# Bluetooth.net
KiCad netlist of a schematic drawn in Altium Designer
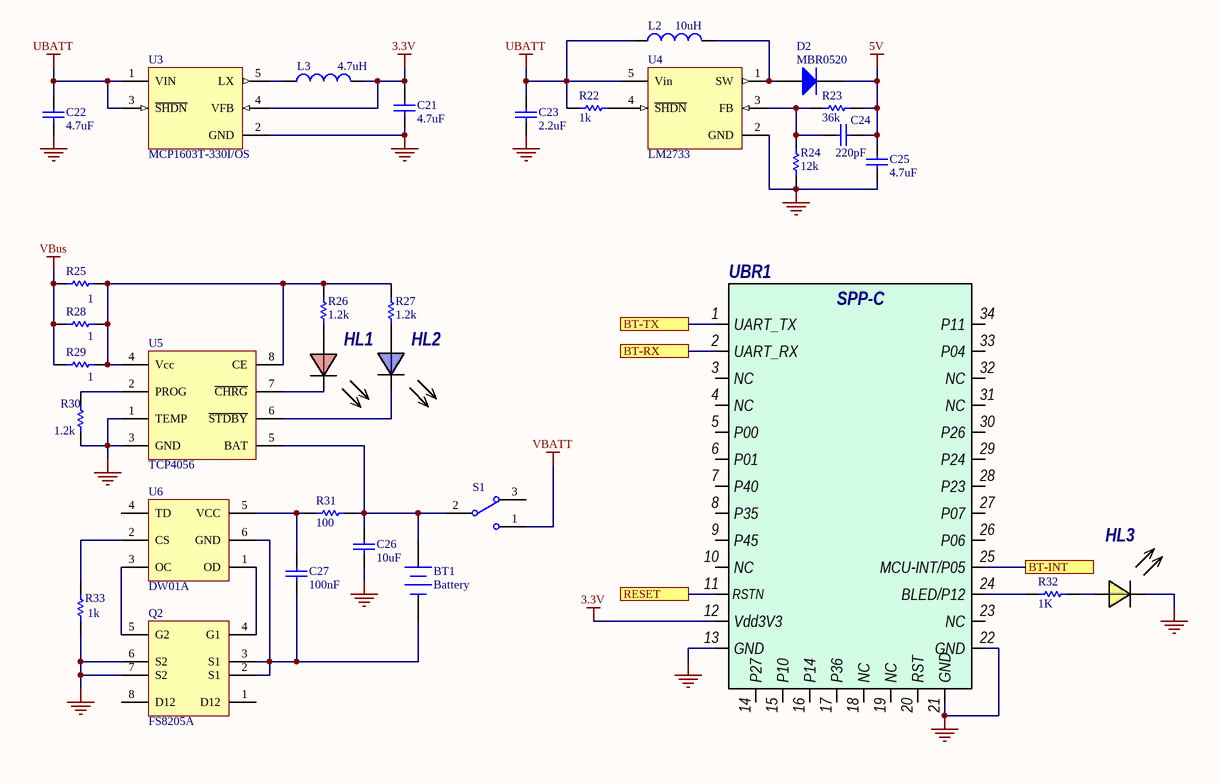
[diagram p0: Bluetooth.SchDoc]

(export (version "E")
  (design (tool "Eeschema 10.0.6"))
  (components
    (comp (ref "BT1")
      (value "Battery")
      (footprint "BAT-2")
      (description "Multicell Battery")
      (fields (field (name "PUBLISHER") "Altium Limited"))
      (libsource (lib "Miscellaneous Devices") (part "Battery"))
    )
    (comp (ref "C21")
      (value "4.7uF")
      (footprint "RAD-0.3")
      (description "Capacitor")
      (fields (field (name "Comment") "Cap") (field (name "PUBLISHER") "Altium Limited"))
      (libsource (lib "Miscellaneous Devices") (part "Cap"))
    )
    (comp (ref "C22")
      (value "4.7uF")
      (footprint "RAD-0.3")
      (description "Capacitor")
      (fields (field (name "Comment") "Cap") (field (name "PUBLISHER") "Altium Limited"))
      (libsource (lib "Miscellaneous Devices") (part "Cap"))
    )
    (comp (ref "C23")
      (value "2.2uF")
      (footprint "RAD-0.3")
      (description "Capacitor")
      (fields (field (name "Comment") "Cap") (field (name "PUBLISHER") "Altium Limited"))
      (libsource (lib "Miscellaneous Devices") (part "Cap"))
    )
    (comp (ref "C24")
      (value "220pF")
      (footprint "RAD-0.3")
      (description "Capacitor")
      (fields (field (name "Comment") "Cap") (field (name "PUBLISHER") "Altium Limited"))
      (libsource (lib "Miscellaneous Devices") (part "Cap"))
    )
    (comp (ref "C25")
      (value "4.7uF")
      (footprint "RAD-0.3")
      (description "Capacitor")
      (fields (field (name "Comment") "Cap") (field (name "PUBLISHER") "Altium Limited"))
      (libsource (lib "Miscellaneous Devices") (part "Cap"))
    )
    (comp (ref "C26")
      (value "10uF")
      (footprint "RAD-0.3")
      (description "Capacitor")
      (fields (field (name "Comment") "Cap") (field (name "PUBLISHER") "Altium Limited"))
      (libsource (lib "Miscellaneous Devices") (part "Cap"))
    )
    (comp (ref "C27")
      (value "100nF")
      (footprint "RAD-0.3")
      (description "Capacitor")
      (fields (field (name "Comment") "Cap") (field (name "PUBLISHER") "Altium Limited"))
      (libsource (lib "Miscellaneous Devices") (part "Cap"))
    )
    (comp (ref "D2")
      (value "MBR0520")
      (footprint "SOD323/A")
      (description "BAT60JFILM")
      (fields (field (name "PUBLISHER") "Altium Limited"))
      (libsource (lib "MB997") (part "BAT60JFILM"))
    )
    (comp (ref "HL1")
      (value "LED_Red")
      (footprint "0603_Red")
      (description "LED Red")
      (libsource (lib "Opto") (part "LED_Red"))
    )
    (comp (ref "HL2")
      (value "LED_Blue")
      (footprint "0603_Blue")
      (description "LED Blue")
      (libsource (lib "Opto") (part "LED_Blue"))
    )
    (comp (ref "HL3")
      (value "Yellow")
      (footprint "0603_Yellow")
      (description "LED Yellow")
      (libsource (lib "Opto") (part "LED_Yellow"))
    )
    (comp (ref "L2")
      (value "10uH")
      (footprint "0402-A")
      (description "Inductor")
      (fields (field (name "PUBLISHER") "Altium Limited"))
      (libsource (lib "Miscellaneous Devices") (part "Inductor"))
    )
    (comp (ref "L3")
      (value "4.7uH")
      (footprint "0402-A")
      (description "Inductor")
      (fields (field (name "PUBLISHER") "Altium Limited"))
      (libsource (lib "Miscellaneous Devices") (part "Inductor"))
    )
    (comp (ref "Q2") (value "FS8205A") (footprint "TSSOP8") (libsource (lib "AU9254") (part "FS8205A")))
    (comp (ref "R22")
      (value "1k")
      (footprint "AXIAL-0.3")
      (description "Resistor")
      (fields (field (name "Comment") "Res1") (field (name "PUBLISHER") "Altium Limited"))
      (libsource (lib "Miscellaneous Devices") (part "Res1"))
    )
    (comp (ref "R23")
      (value "36k")
      (footprint "AXIAL-0.3")
      (description "Resistor")
      (fields (field (name "Comment") "Res1") (field (name "PUBLISHER") "Altium Limited"))
      (libsource (lib "Miscellaneous Devices") (part "Res1"))
    )
    (comp (ref "R24")
      (value "12k")
      (footprint "AXIAL-0.3")
      (description "Resistor")
      (fields (field (name "Comment") "Res1") (field (name "PUBLISHER") "Altium Limited"))
      (libsource (lib "Miscellaneous Devices") (part "Res1"))
    )
    (comp (ref "R25")
      (value "1")
      (footprint "AXIAL-0.3")
      (description "Resistor")
      (fields (field (name "Comment") "Res1") (field (name "PUBLISHER") "Altium Limited"))
      (libsource (lib "Miscellaneous Devices") (part "Res1"))
    )
    (comp (ref "R26")
      (value "1.2k")
      (footprint "AXIAL-0.3")
      (description "Resistor")
      (fields (field (name "Comment") "Res1") (field (name "PUBLISHER") "Altium Limited"))
      (libsource (lib "Miscellaneous Devices") (part "Res1"))
    )
    (comp (ref "R27")
      (value "1.2k")
      (footprint "AXIAL-0.3")
      (description "Resistor")
      (fields (field (name "Comment") "Res1") (field (name "PUBLISHER") "Altium Limited"))
      (libsource (lib "Miscellaneous Devices") (part "Res1"))
    )
    (comp (ref "R28")
      (value "1")
      (footprint "AXIAL-0.3")
      (description "Resistor")
      (fields (field (name "Comment") "Res1") (field (name "PUBLISHER") "Altium Limited"))
      (libsource (lib "Miscellaneous Devices") (part "Res1"))
    )
    (comp (ref "R29")
      (value "1")
      (footprint "AXIAL-0.3")
      (description "Resistor")
      (fields (field (name "Comment") "Res1") (field (name "PUBLISHER") "Altium Limited"))
      (libsource (lib "Miscellaneous Devices") (part "Res1"))
    )
    (comp (ref "R30")
      (value "1.2k")
      (footprint "AXIAL-0.3")
      (description "Resistor")
      (fields (field (name "Comment") "Res1") (field (name "PUBLISHER") "Altium Limited"))
      (libsource (lib "Miscellaneous Devices") (part "Res1"))
    )
    (comp (ref "R31")
      (value "100")
      (footprint "AXIAL-0.3")
      (description "Resistor")
      (fields (field (name "Comment") "Res1") (field (name "PUBLISHER") "Altium Limited"))
      (libsource (lib "Miscellaneous Devices") (part "Res1"))
    )
    (comp (ref "R32")
      (value "1K")
      (footprint "AXIAL-0.3")
      (description "Resistor")
      (fields (field (name "Comment") "Res1") (field (name "PUBLISHER") "Altium Limited"))
      (libsource (lib "Miscellaneous Devices") (part "Res1"))
    )
    (comp (ref "R33")
      (value "1k")
      (footprint "AXIAL-0.3")
      (description "Resistor")
      (fields (field (name "Comment") "Res1") (field (name "PUBLISHER") "Altium Limited"))
      (libsource (lib "Miscellaneous Devices") (part "Res1"))
    )
    (comp (ref "S1")
      (value "SW-SPDT")
      (footprint "TL36WW15050")
      (description "SPDT Subminiature Toggle Switch, Right Angle Mounting, Vertical Actuation")
      (fields (field (name "PUBLISHER") "Altium Limited"))
      (libsource (lib "Miscellaneous Devices") (part "SW-SPDT"))
    )
    (comp (ref "U3")
      (value "MCP1603T-330I/OS")
      (footprint "SOT23_5")
      (description "500mA Synchronous Buck Regulator, 3.3V, 2.0 MHz, 5-Pin TSOT, Industrial Temperature, Tape and Reel")
      (fields (field (name "PUBLISHER") "Altium Limited"))
      (libsource (lib "AU9254") (part "MCP1603T-330I/OS"))
    )
    (comp (ref "U4")
      (value "LM2733")
      (footprint "SOT23_5")
      (description "0.6/1.6 MHz Boost Converters With 40V Internal FET Switch")
      (fields (field (name "PUBLISHER") "Altium Limited"))
      (libsource (lib "AU9254") (part "LM2733"))
    )
    (comp (ref "U5") (value "TCP4056") (footprint "SO8") (libsource (lib "AU9254") (part "TP4056")))
    (comp (ref "U6") (value "DW01A") (footprint "SOT23_6") (libsource (lib "AU9254") (part "DW01A")))
    (comp (ref "UBR1")
      (value "SPP-C")
      (footprint "SPP-C")
      (description "Bluetooth Module")
      (libsource (lib "AU9254") (part "SPP-C"))
    )
  )
  (nets
    (net (code "1") (name "/BT-INT") (class "Default")
      (node (ref "UBR1") (pin "25") (pinfunction "MCU-INT/P05_25") (pintype "passive"))
    )
    (net (code "2") (name "/BT-RX") (class "Default")
      (node (ref "UBR1") (pin "2") (pinfunction "UART_RX_2") (pintype "passive"))
    )
    (net (code "3") (name "/BT-TX") (class "Default")
      (node (ref "UBR1") (pin "1") (pinfunction "UART_TX_1") (pintype "passive"))
    )
    (net (code "4") (name "/RESET") (class "Default")
      (node (ref "UBR1") (pin "11") (pinfunction "RSTN_11") (pintype "passive"))
    )
    (net (code "5") (name "3.3V") (class "Default")
      (node (ref "C21") (pin "2") (pinfunction "2_2") (pintype "passive"))
      (node (ref "L3") (pin "2") (pinfunction "2_2") (pintype "passive"))
      (node (ref "U3") (pin "4") (pinfunction "VFB_4") (pintype "input"))
      (node (ref "UBR1") (pin "12") (pinfunction "Vdd3V3_12") (pintype "power_in"))
    )
    (net (code "6") (name "5V") (class "Default")
      (node (ref "C24") (pin "1") (pinfunction "1_1") (pintype "passive"))
      (node (ref "C25") (pin "2") (pinfunction "2_2") (pintype "passive"))
      (node (ref "D2") (pin "2") (pinfunction "K_2") (pintype "passive"))
      (node (ref "R23") (pin "1") (pinfunction "1_1") (pintype "passive"))
    )
    (net (code "7") (name "GND") (class "Default")
      (node (ref "C21") (pin "1") (pinfunction "1_1") (pintype "passive"))
      (node (ref "C22") (pin "1") (pinfunction "1_1") (pintype "passive"))
      (node (ref "C23") (pin "1") (pinfunction "1_1") (pintype "passive"))
      (node (ref "C25") (pin "1") (pinfunction "1_1") (pintype "passive"))
      (node (ref "C26") (pin "1") (pinfunction "1_1") (pintype "passive"))
      (node (ref "HL3") (pin "C") (pinfunction "C_C") (pintype "passive"))
      (node (ref "Q2") (pin "6") (pinfunction "S2_6") (pintype "passive"))
      (node (ref "Q2") (pin "7") (pinfunction "S2_7") (pintype "passive"))
      (node (ref "R24") (pin "2") (pinfunction "2_2") (pintype "passive"))
      (node (ref "R30") (pin "1") (pinfunction "1_1") (pintype "passive"))
      (node (ref "R33") (pin "1") (pinfunction "1_1") (pintype "passive"))
      (node (ref "U3") (pin "2") (pinfunction "GND_2") (pintype "power_in"))
      (node (ref "U4") (pin "2") (pinfunction "GND_2") (pintype "power_in"))
      (node (ref "U5") (pin "1") (pinfunction "TEMP_1") (pintype "passive"))
      (node (ref "U5") (pin "3") (pinfunction "GND_3") (pintype "power_in"))
      (node (ref "UBR1") (pin "13") (pinfunction "GND_13") (pintype "power_in"))
      (node (ref "UBR1") (pin "21") (pinfunction "GND_21") (pintype "power_in"))
      (node (ref "UBR1") (pin "22") (pinfunction "GND_22") (pintype "power_in"))
    )
    (net (code "8") (name "Net-(BT1-+)") (class "Default")
      (node (ref "BT1") (pin "1") (pinfunction "+_1") (pintype "passive"))
      (node (ref "C26") (pin "2") (pinfunction "2_2") (pintype "passive"))
      (node (ref "R31") (pin "1") (pinfunction "1_1") (pintype "passive"))
      (node (ref "S1") (pin "2") (pinfunction "2_2") (pintype "passive"))
      (node (ref "U5") (pin "5") (pinfunction "BAT_5") (pintype "power_in"))
    )
    (net (code "9") (name "Net-(BT1--)") (class "Default")
      (node (ref "BT1") (pin "2") (pinfunction "-_2") (pintype "passive"))
      (node (ref "C27") (pin "1") (pinfunction "1_1") (pintype "passive"))
      (node (ref "Q2") (pin "2") (pinfunction "S1_2") (pintype "passive"))
      (node (ref "Q2") (pin "3") (pinfunction "S1_3") (pintype "passive"))
      (node (ref "U6") (pin "6") (pinfunction "GND_6") (pintype "passive"))
    )
    (net (code "10") (name "Net-(D2-A)") (class "Default")
      (node (ref "D2") (pin "1") (pinfunction "A_1") (pintype "passive"))
      (node (ref "L2") (pin "2") (pinfunction "2_2") (pintype "passive"))
      (node (ref "U4") (pin "1") (pinfunction "SW_1") (pintype "output"))
    )
    (net (code "11") (name "Net-(HL1-PadA)") (class "Default")
      (node (ref "HL1") (pin "A") (pinfunction "A_A") (pintype "passive"))
      (node (ref "R26") (pin "1") (pinfunction "1_1") (pintype "passive"))
    )
    (net (code "12") (name "Net-(HL2-PadA)") (class "Default")
      (node (ref "HL2") (pin "A") (pinfunction "A_A") (pintype "passive"))
      (node (ref "R27") (pin "1") (pinfunction "1_1") (pintype "passive"))
    )
    (net (code "13") (name "Net-(HL3-PadA)") (class "Default")
      (node (ref "HL3") (pin "A") (pinfunction "A_A") (pintype "passive"))
      (node (ref "R32") (pin "1") (pinfunction "1_1") (pintype "passive"))
    )
    (net (code "14") (name "Net-(Q2-G1)") (class "Default")
      (node (ref "Q2") (pin "4") (pinfunction "G1_4") (pintype "passive"))
      (node (ref "U6") (pin "1") (pinfunction "OD_1") (pintype "passive"))
    )
    (net (code "15") (name "Net-(Q2-G2)") (class "Default")
      (node (ref "Q2") (pin "5") (pinfunction "G2_5") (pintype "passive"))
      (node (ref "U6") (pin "3") (pinfunction "OC_3") (pintype "passive"))
    )
    (net (code "16") (name "Net-(U3-LX)") (class "Default")
      (node (ref "L3") (pin "1") (pinfunction "1_1") (pintype "passive"))
      (node (ref "U3") (pin "5") (pinfunction "LX_5") (pintype "output"))
    )
    (net (code "17") (name "Net-(U4-FB)") (class "Default")
      (node (ref "C24") (pin "2") (pinfunction "2_2") (pintype "passive"))
      (node (ref "R23") (pin "2") (pinfunction "2_2") (pintype "passive"))
      (node (ref "R24") (pin "1") (pinfunction "1_1") (pintype "passive"))
      (node (ref "U4") (pin "3") (pinfunction "FB_3") (pintype "input"))
    )
    (net (code "18") (name "Net-(U4-~{SHDN})") (class "Default")
      (node (ref "R22") (pin "1") (pinfunction "1_1") (pintype "passive"))
      (node (ref "U4") (pin "4") (pinfunction "~{SHDN}_4") (pintype "input"))
    )
    (net (code "19") (name "Net-(U5-CE)") (class "Default")
      (node (ref "R25") (pin "1") (pinfunction "1_1") (pintype "passive"))
      (node (ref "R26") (pin "2") (pinfunction "2_2") (pintype "passive"))
      (node (ref "R27") (pin "2") (pinfunction "2_2") (pintype "passive"))
      (node (ref "R28") (pin "1") (pinfunction "1_1") (pintype "passive"))
      (node (ref "R29") (pin "1") (pinfunction "1_1") (pintype "passive"))
      (node (ref "U5") (pin "4") (pinfunction "Vcc_4") (pintype "power_in"))
      (node (ref "U5") (pin "8") (pinfunction "CE_8") (pintype "passive"))
    )
    (net (code "20") (name "Net-(U5-PROG)") (class "Default")
      (node (ref "R30") (pin "2") (pinfunction "2_2") (pintype "passive"))
      (node (ref "U5") (pin "2") (pinfunction "PROG_2") (pintype "passive"))
    )
    (net (code "21") (name "Net-(U5-~{CHRG})") (class "Default")
      (node (ref "HL1") (pin "C") (pinfunction "C_C") (pintype "passive"))
      (node (ref "U5") (pin "7") (pinfunction "~{CHRG}_7") (pintype "open_collector"))
    )
    (net (code "22") (name "Net-(U5-~{STDBY})") (class "Default")
      (node (ref "HL2") (pin "C") (pinfunction "C_C") (pintype "passive"))
      (node (ref "U5") (pin "6") (pinfunction "~{STDBY}_6") (pintype "open_collector"))
    )
    (net (code "23") (name "Net-(U6-CS)") (class "Default")
      (node (ref "R33") (pin "2") (pinfunction "2_2") (pintype "passive"))
      (node (ref "U6") (pin "2") (pinfunction "CS_2") (pintype "passive"))
    )
    (net (code "24") (name "Net-(U6-VCC)") (class "Default")
      (node (ref "C27") (pin "2") (pinfunction "2_2") (pintype "passive"))
      (node (ref "R31") (pin "2") (pinfunction "2_2") (pintype "passive"))
      (node (ref "U6") (pin "5") (pinfunction "VCC_5") (pintype "passive"))
    )
    (net (code "25") (name "Net-(UBR1-BLED{slash}P12)") (class "Default")
      (node (ref "R32") (pin "2") (pinfunction "2_2") (pintype "passive"))
      (node (ref "UBR1") (pin "24") (pinfunction "BLED/P12_24") (pintype "passive"))
    )
    (net (code "26") (name "UBATT") (class "Default")
      (node (ref "C22") (pin "2") (pinfunction "2_2") (pintype "passive"))
      (node (ref "C23") (pin "2") (pinfunction "2_2") (pintype "passive"))
      (node (ref "L2") (pin "1") (pinfunction "1_1") (pintype "passive"))
      (node (ref "R22") (pin "2") (pinfunction "2_2") (pintype "passive"))
      (node (ref "U3") (pin "1") (pinfunction "VIN_1") (pintype "power_in"))
      (node (ref "U3") (pin "3") (pinfunction "~{SHDN}_3") (pintype "input"))
      (node (ref "U4") (pin "5") (pinfunction "Vin_5") (pintype "power_in"))
    )
    (net (code "27") (name "VBATT") (class "Default")
      (node (ref "S1") (pin "1") (pinfunction "1_1") (pintype "passive"))
    )
    (net (code "28") (name "VBus") (class "Default")
      (node (ref "R25") (pin "2") (pinfunction "2_2") (pintype "passive"))
      (node (ref "R28") (pin "2") (pinfunction "2_2") (pintype "passive"))
      (node (ref "R29") (pin "2") (pinfunction "2_2") (pintype "passive"))
    )
    (net (code "29") (name "unconnected-(Q2-D12-Pad1)") (class "Default")
      (node (ref "Q2") (pin "1") (pinfunction "D12_1") (pintype "passive"))
    )
    (net (code "30") (name "unconnected-(Q2-D12-Pad8)") (class "Default")
      (node (ref "Q2") (pin "8") (pinfunction "D12_8") (pintype "passive"))
    )
    (net (code "31") (name "unconnected-(S1-Pad3)") (class "Default")
      (node (ref "S1") (pin "3") (pinfunction "3_3") (pintype "passive"))
    )
    (net (code "32") (name "unconnected-(U6-TD-Pad4)") (class "Default")
      (node (ref "U6") (pin "4") (pinfunction "TD_4") (pintype "passive"))
    )
    (net (code "33") (name "unconnected-(UBR1-NC-Pad3)") (class "Default")
      (node (ref "UBR1") (pin "3") (pinfunction "NC_3") (pintype "passive"))
    )
    (net (code "34") (name "unconnected-(UBR1-NC-Pad4)") (class "Default")
      (node (ref "UBR1") (pin "4") (pinfunction "NC_4") (pintype "passive"))
    )
    (net (code "35") (name "unconnected-(UBR1-NC-Pad10)") (class "Default")
      (node (ref "UBR1") (pin "10") (pinfunction "NC_10") (pintype "passive"))
    )
    (net (code "36") (name "unconnected-(UBR1-NC-Pad18)") (class "Default")
      (node (ref "UBR1") (pin "18") (pinfunction "NC_18") (pintype "passive"))
    )
    (net (code "37") (name "unconnected-(UBR1-NC-Pad19)") (class "Default")
      (node (ref "UBR1") (pin "19") (pinfunction "NC_19") (pintype "passive"))
    )
    (net (code "38") (name "unconnected-(UBR1-NC-Pad23)") (class "Default")
      (node (ref "UBR1") (pin "23") (pinfunction "NC_23") (pintype "passive"))
    )
    (net (code "39") (name "unconnected-(UBR1-NC-Pad31)") (class "Default")
      (node (ref "UBR1") (pin "31") (pinfunction "NC_31") (pintype "passive"))
    )
    (net (code "40") (name "unconnected-(UBR1-NC-Pad32)") (class "Default")
      (node (ref "UBR1") (pin "32") (pinfunction "NC_32") (pintype "passive"))
    )
    (net (code "41") (name "unconnected-(UBR1-P00-Pad5)") (class "Default")
      (node (ref "UBR1") (pin "5") (pinfunction "P00_5") (pintype "passive"))
    )
    (net (code "42") (name "unconnected-(UBR1-P01-Pad6)") (class "Default")
      (node (ref "UBR1") (pin "6") (pinfunction "P01_6") (pintype "passive"))
    )
    (net (code "43") (name "unconnected-(UBR1-P04-Pad33)") (class "Default")
      (node (ref "UBR1") (pin "33") (pinfunction "P04_33") (pintype "passive"))
    )
    (net (code "44") (name "unconnected-(UBR1-P06-Pad26)") (class "Default")
      (node (ref "UBR1") (pin "26") (pinfunction "P06_26") (pintype "passive"))
    )
    (net (code "45") (name "unconnected-(UBR1-P07-Pad27)") (class "Default")
      (node (ref "UBR1") (pin "27") (pinfunction "P07_27") (pintype "passive"))
    )
    (net (code "46") (name "unconnected-(UBR1-P10-Pad15)") (class "Default")
      (node (ref "UBR1") (pin "15") (pinfunction "P10_15") (pintype "passive"))
    )
    (net (code "47") (name "unconnected-(UBR1-P11-Pad34)") (class "Default")
      (node (ref "UBR1") (pin "34") (pinfunction "P11_34") (pintype "passive"))
    )
    (net (code "48") (name "unconnected-(UBR1-P14-Pad16)") (class "Default")
      (node (ref "UBR1") (pin "16") (pinfunction "P14_16") (pintype "passive"))
    )
    (net (code "49") (name "unconnected-(UBR1-P23-Pad28)") (class "Default")
      (node (ref "UBR1") (pin "28") (pinfunction "P23_28") (pintype "passive"))
    )
    (net (code "50") (name "unconnected-(UBR1-P24-Pad29)") (class "Default")
      (node (ref "UBR1") (pin "29") (pinfunction "P24_29") (pintype "passive"))
    )
    (net (code "51") (name "unconnected-(UBR1-P26-Pad30)") (class "Default")
      (node (ref "UBR1") (pin "30") (pinfunction "P26_30") (pintype "passive"))
    )
    (net (code "52") (name "unconnected-(UBR1-P27-Pad14)") (class "Default")
      (node (ref "UBR1") (pin "14") (pinfunction "P27_14") (pintype "passive"))
    )
    (net (code "53") (name "unconnected-(UBR1-P35-Pad8)") (class "Default")
      (node (ref "UBR1") (pin "8") (pinfunction "P35_8") (pintype "passive"))
    )
    (net (code "54") (name "unconnected-(UBR1-P36-Pad17)") (class "Default")
      (node (ref "UBR1") (pin "17") (pinfunction "P36_17") (pintype "passive"))
    )
    (net (code "55") (name "unconnected-(UBR1-P40-Pad7)") (class "Default")
      (node (ref "UBR1") (pin "7") (pinfunction "P40_7") (pintype "passive"))
    )
    (net (code "56") (name "unconnected-(UBR1-P45-Pad9)") (class "Default")
      (node (ref "UBR1") (pin "9") (pinfunction "P45_9") (pintype "passive"))
    )
    (net (code "57") (name "unconnected-(UBR1-RST-Pad20)") (class "Default")
      (node (ref "UBR1") (pin "20") (pinfunction "RST_20") (pintype "passive"))
    )
  )
)
